# ESP32_Sch.net
KiCad netlist of a schematic drawn in Altium Designer
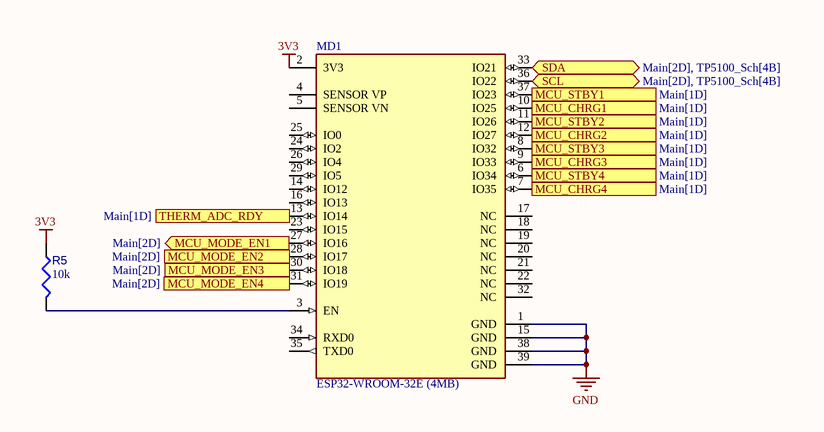
[diagram p0: ESP32_Sch.SchDoc]

(export (version "E")
  (design (tool "Eeschema 10.0.6"))
  (components
    (comp (ref "MD1")
      (value "ESP32-WROOM-32E (4MB)")
      (footprint "FP-ESP32-WROOM-32E_4MB-MFG")
      (description "RX TXRX MOD WIFI TRACE ANT SMD")
      (libsource (lib "Altium Content Vault") (part "7f842c3463a9561e2f6f9fdcd687e0f"))
    )
    (comp (ref "R5")
      (value "10k")
      (footprint "RESC0402(1005)_L")
      (description "10K 0.063W 1% 0402 (1005 Metric)  SMD")
      (fields (field (name "POWER") "63mW") (field (name "TOLERANCE") "1%"))
      (libsource (lib "ZionTech") (part "10KR2F"))
    )
  )
  (nets
    (net (code "1") (name "/MCU_CHRG1") (class "Default")
      (node (ref "MD1") (pin "10") (pinfunction "IO25_10") (pintype "bidirectional"))
    )
    (net (code "2") (name "/MCU_CHRG2") (class "Default")
      (node (ref "MD1") (pin "12") (pinfunction "IO27_12") (pintype "bidirectional"))
    )
    (net (code "3") (name "/MCU_CHRG3") (class "Default")
      (node (ref "MD1") (pin "9") (pinfunction "IO33_9") (pintype "bidirectional"))
    )
    (net (code "4") (name "/MCU_CHRG4") (class "Default")
      (node (ref "MD1") (pin "7") (pinfunction "IO35_7") (pintype "bidirectional"))
    )
    (net (code "5") (name "/MCU_MODE_EN1") (class "Default")
      (node (ref "MD1") (pin "27") (pinfunction "IO16_27") (pintype "bidirectional"))
    )
    (net (code "6") (name "/MCU_MODE_EN2") (class "Default")
      (node (ref "MD1") (pin "28") (pinfunction "IO17_28") (pintype "bidirectional"))
    )
    (net (code "7") (name "/MCU_MODE_EN3") (class "Default")
      (node (ref "MD1") (pin "30") (pinfunction "IO18_30") (pintype "bidirectional"))
    )
    (net (code "8") (name "/MCU_MODE_EN4") (class "Default")
      (node (ref "MD1") (pin "31") (pinfunction "IO19_31") (pintype "bidirectional"))
    )
    (net (code "9") (name "/MCU_STBY1") (class "Default")
      (node (ref "MD1") (pin "37") (pinfunction "IO23_37") (pintype "bidirectional"))
    )
    (net (code "10") (name "/MCU_STBY2") (class "Default")
      (node (ref "MD1") (pin "11") (pinfunction "IO26_11") (pintype "bidirectional"))
    )
    (net (code "11") (name "/MCU_STBY3") (class "Default")
      (node (ref "MD1") (pin "8") (pinfunction "IO32_8") (pintype "bidirectional"))
    )
    (net (code "12") (name "/MCU_STBY4") (class "Default")
      (node (ref "MD1") (pin "6") (pinfunction "IO34_6") (pintype "bidirectional"))
    )
    (net (code "13") (name "/SCL") (class "Default")
      (node (ref "MD1") (pin "36") (pinfunction "IO22_36") (pintype "bidirectional"))
    )
    (net (code "14") (name "/SDA") (class "Default")
      (node (ref "MD1") (pin "33") (pinfunction "IO21_33") (pintype "bidirectional"))
    )
    (net (code "15") (name "/THERM_ADC_RDY") (class "Default")
      (node (ref "MD1") (pin "13") (pinfunction "IO14_13") (pintype "bidirectional"))
    )
    (net (code "16") (name "3V3") (class "Default")
      (node (ref "MD1") (pin "2") (pinfunction "3V3_2") (pintype "power_in"))
      (node (ref "R5") (pin "1") (pinfunction "1_1") (pintype "passive"))
    )
    (net (code "17") (name "GND") (class "Default")
      (node (ref "MD1") (pin "1") (pinfunction "GND_1") (pintype "power_in"))
      (node (ref "MD1") (pin "15") (pinfunction "GND_15") (pintype "power_in"))
      (node (ref "MD1") (pin "38") (pinfunction "GND_38") (pintype "power_in"))
      (node (ref "MD1") (pin "39") (pinfunction "GND_39") (pintype "power_in"))
    )
    (net (code "18") (name "Net-(MD1-EN)") (class "Default")
      (node (ref "MD1") (pin "3") (pinfunction "EN_3") (pintype "input"))
      (node (ref "R5") (pin "2") (pinfunction "2_2") (pintype "passive"))
    )
    (net (code "19") (name "unconnected-(MD1-IO0-Pad25)") (class "Default")
      (node (ref "MD1") (pin "25") (pinfunction "IO0_25") (pintype "bidirectional"))
    )
    (net (code "20") (name "unconnected-(MD1-IO2-Pad24)") (class "Default")
      (node (ref "MD1") (pin "24") (pinfunction "IO2_24") (pintype "bidirectional"))
    )
    (net (code "21") (name "unconnected-(MD1-IO4-Pad26)") (class "Default")
      (node (ref "MD1") (pin "26") (pinfunction "IO4_26") (pintype "bidirectional"))
    )
    (net (code "22") (name "unconnected-(MD1-IO5-Pad29)") (class "Default")
      (node (ref "MD1") (pin "29") (pinfunction "IO5_29") (pintype "bidirectional"))
    )
    (net (code "23") (name "unconnected-(MD1-IO12-Pad14)") (class "Default")
      (node (ref "MD1") (pin "14") (pinfunction "IO12_14") (pintype "bidirectional"))
    )
    (net (code "24") (name "unconnected-(MD1-IO13-Pad16)") (class "Default")
      (node (ref "MD1") (pin "16") (pinfunction "IO13_16") (pintype "bidirectional"))
    )
    (net (code "25") (name "unconnected-(MD1-IO15-Pad23)") (class "Default")
      (node (ref "MD1") (pin "23") (pinfunction "IO15_23") (pintype "bidirectional"))
    )
    (net (code "26") (name "unconnected-(MD1-NC-Pad17)") (class "Default")
      (node (ref "MD1") (pin "17") (pinfunction "NC_17") (pintype "passive"))
    )
    (net (code "27") (name "unconnected-(MD1-NC-Pad18)") (class "Default")
      (node (ref "MD1") (pin "18") (pinfunction "NC_18") (pintype "passive"))
    )
    (net (code "28") (name "unconnected-(MD1-NC-Pad19)") (class "Default")
      (node (ref "MD1") (pin "19") (pinfunction "NC_19") (pintype "passive"))
    )
    (net (code "29") (name "unconnected-(MD1-NC-Pad20)") (class "Default")
      (node (ref "MD1") (pin "20") (pinfunction "NC_20") (pintype "passive"))
    )
    (net (code "30") (name "unconnected-(MD1-NC-Pad21)") (class "Default")
      (node (ref "MD1") (pin "21") (pinfunction "NC_21") (pintype "passive"))
    )
    (net (code "31") (name "unconnected-(MD1-NC-Pad22)") (class "Default")
      (node (ref "MD1") (pin "22") (pinfunction "NC_22") (pintype "passive"))
    )
    (net (code "32") (name "unconnected-(MD1-NC-Pad32)") (class "Default")
      (node (ref "MD1") (pin "32") (pinfunction "NC_32") (pintype "passive"))
    )
    (net (code "33") (name "unconnected-(MD1-RXD0-Pad34)") (class "Default")
      (node (ref "MD1") (pin "34") (pinfunction "RXD0_34") (pintype "input"))
    )
    (net (code "34") (name "unconnected-(MD1-SENSOR_VN-Pad5)") (class "Default")
      (node (ref "MD1") (pin "5") (pinfunction "SENSOR_VN_5") (pintype "passive"))
    )
    (net (code "35") (name "unconnected-(MD1-SENSOR_VP-Pad4)") (class "Default")
      (node (ref "MD1") (pin "4") (pinfunction "SENSOR_VP_4") (pintype "passive"))
    )
    (net (code "36") (name "unconnected-(MD1-TXD0-Pad35)") (class "Default")
      (node (ref "MD1") (pin "35") (pinfunction "TXD0_35") (pintype "output"))
    )
  )
)
